# detector328p-au.net
KiCad netlist of a schematic drawn in EAGLE
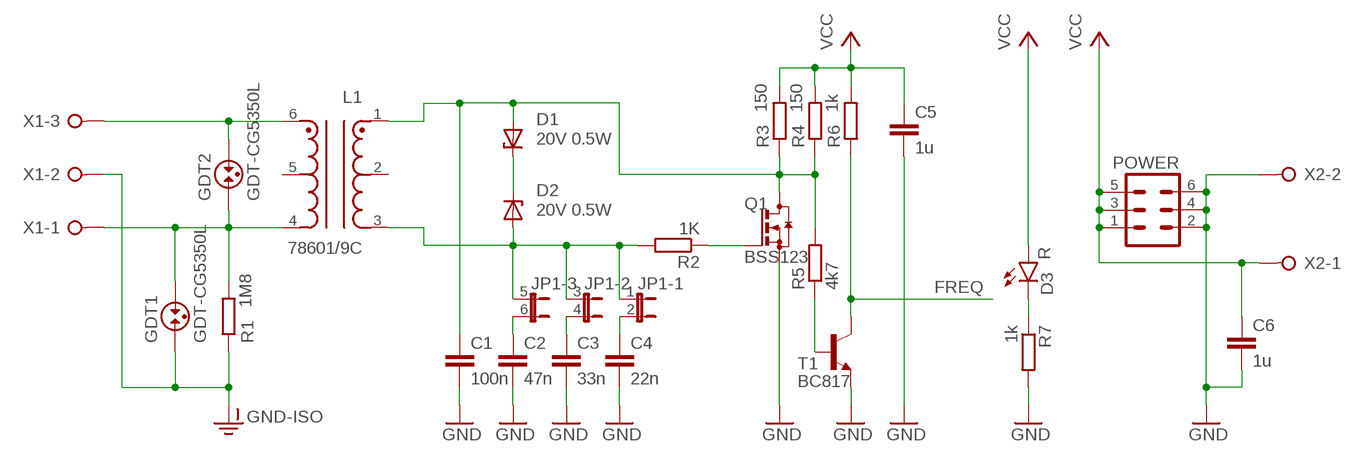
[diagram p0: schematic, sheet 1]
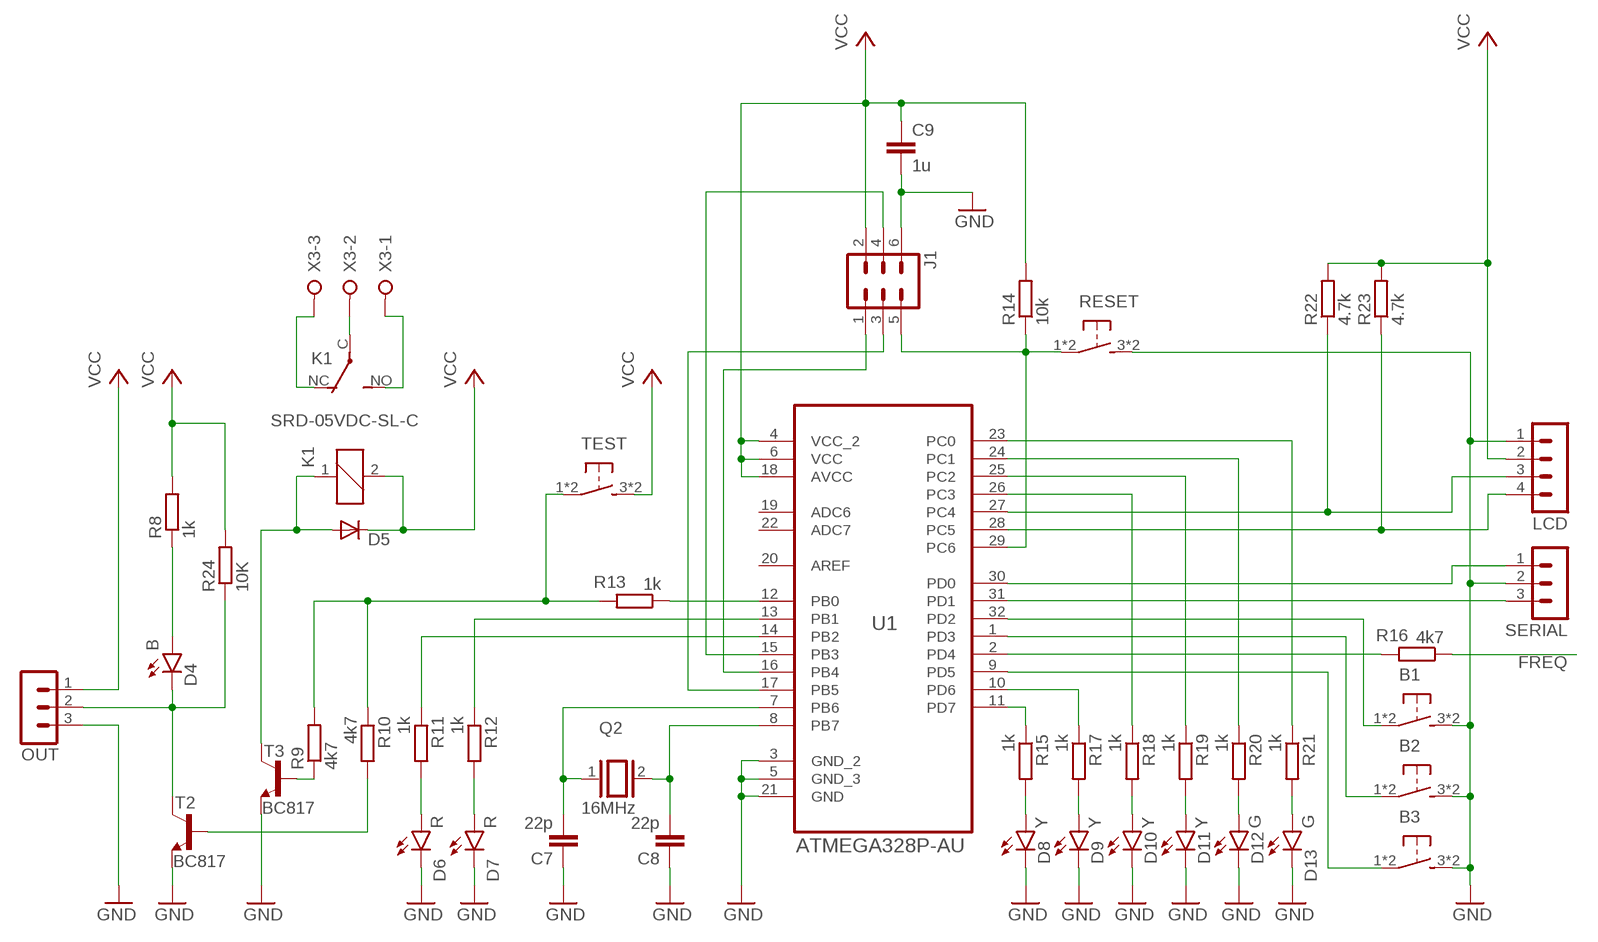
[diagram p1: schematic, sheet 2]

(export (version "E")
  (design (tool "Eeschema 10.0.6"))
  (components
    (comp (ref "B1")
      (value "10-XX")
      (footprint "eagle-import:B3F-10XX")
      (fields (field (name "MPN") "B3F-1000"))
      (libsource (lib "eagle-import") (part "10-XX"))
    )
    (comp (ref "B2")
      (value "10-XX")
      (footprint "eagle-import:B3F-10XX")
      (fields (field (name "MPN") "B3F-1000"))
      (libsource (lib "eagle-import") (part "10-XX"))
    )
    (comp (ref "B3")
      (value "10-XX")
      (footprint "eagle-import:B3F-10XX")
      (fields (field (name "MPN") "B3F-1000"))
      (libsource (lib "eagle-import") (part "10-XX"))
    )
    (comp (ref "C7")
      (value "22p")
      (footprint "eagle-import:C0603")
      (libsource (lib "eagle-import") (part "resistor_C-EUC0603"))
    )
    (comp (ref "C8")
      (value "22p")
      (footprint "eagle-import:C0603")
      (libsource (lib "eagle-import") (part "resistor_C-EUC0603"))
    )
    (comp (ref "C9")
      (value "1u")
      (footprint "eagle-import:C0603")
      (libsource (lib "eagle-import") (part "C-EUC0603"))
    )
    (comp (ref "D4")
      (value "B")
      (footprint "eagle-import:LED-0603")
      (libsource (lib "eagle-import") (part "LED0603"))
    )
    (comp (ref "D5")
      (value "DIODE-SOD80C")
      (footprint "eagle-import:SOD80C")
      (libsource (lib "eagle-import") (part "DIODE-SOD80C"))
    )
    (comp (ref "D6")
      (value "R")
      (footprint "eagle-import:LED-0603")
      (libsource (lib "eagle-import") (part "LED0603"))
    )
    (comp (ref "D7")
      (value "R")
      (footprint "eagle-import:LED-0603")
      (libsource (lib "eagle-import") (part "LED0603"))
    )
    (comp (ref "D8")
      (value "Y")
      (footprint "eagle-import:LED-0603")
      (libsource (lib "eagle-import") (part "LED0603"))
    )
    (comp (ref "D9")
      (value "Y")
      (footprint "eagle-import:LED-0603")
      (libsource (lib "eagle-import") (part "LED0603"))
    )
    (comp (ref "D10")
      (value "Y")
      (footprint "eagle-import:LED-0603")
      (libsource (lib "eagle-import") (part "LED0603"))
    )
    (comp (ref "D11")
      (value "Y")
      (footprint "eagle-import:LED-0603")
      (libsource (lib "eagle-import") (part "LED0603"))
    )
    (comp (ref "D12")
      (value "G")
      (footprint "eagle-import:LED-0603")
      (libsource (lib "eagle-import") (part "LED0603"))
    )
    (comp (ref "D13")
      (value "G")
      (footprint "eagle-import:LED-0603")
      (libsource (lib "eagle-import") (part "LED0603"))
    )
    (comp (ref "J1")
      (value "MA03-2")
      (footprint "eagle-import:MA03-2")
      (libsource (lib "eagle-import") (part "MA03-2"))
    )
    (comp (ref "K1")
      (value "SRD-05VDC-SL-C")
      (footprint "eagle-import:JS-M")
      (libsource (lib "eagle-import") (part "SRD--SL-C05VDC"))
    )
    (comp (ref "LCD")
      (value "MA04-1")
      (footprint "eagle-import:MA04-1")
      (libsource (lib "eagle-import") (part "MA04-1"))
    )
    (comp (ref "OUT")
      (value "MA03-1")
      (footprint "eagle-import:MA03-1")
      (libsource (lib "eagle-import") (part "MA03-1"))
    )
    (comp (ref "Q2")
      (value "16MHz")
      (footprint "eagle-import:QS")
      (libsource (lib "eagle-import") (part "XTAL/S"))
    )
    (comp (ref "R8")
      (value "1k")
      (footprint "eagle-import:R0603")
      (libsource (lib "eagle-import") (part "resistor_R-EU_R0603"))
    )
    (comp (ref "R9")
      (value "4k7")
      (footprint "eagle-import:R0603")
      (libsource (lib "eagle-import") (part "resistor_R-EU_R0603"))
    )
    (comp (ref "R10")
      (value "4k7")
      (footprint "eagle-import:R0603")
      (libsource (lib "eagle-import") (part "resistor_R-EU_R0603"))
    )
    (comp (ref "R11")
      (value "1k")
      (footprint "eagle-import:R0603")
      (libsource (lib "eagle-import") (part "resistor_R-EU_R0603"))
    )
    (comp (ref "R12")
      (value "1k")
      (footprint "eagle-import:R0603")
      (libsource (lib "eagle-import") (part "resistor_R-EU_R0603"))
    )
    (comp (ref "R13")
      (value "1k")
      (footprint "eagle-import:R0603")
      (libsource (lib "eagle-import") (part "resistor_R-EU_R0603"))
    )
    (comp (ref "R14")
      (value "10k")
      (footprint "eagle-import:R0603")
      (libsource (lib "eagle-import") (part "resistor_R-EU_R0603"))
    )
    (comp (ref "R15")
      (value "1k")
      (footprint "eagle-import:R0603")
      (libsource (lib "eagle-import") (part "resistor_R-EU_R0603"))
    )
    (comp (ref "R16")
      (value "4k7")
      (footprint "eagle-import:R0603")
      (libsource (lib "eagle-import") (part "resistor_R-EU_R0603"))
    )
    (comp (ref "R17")
      (value "1k")
      (footprint "eagle-import:R0603")
      (libsource (lib "eagle-import") (part "resistor_R-EU_R0603"))
    )
    (comp (ref "R18")
      (value "1k")
      (footprint "eagle-import:R0603")
      (libsource (lib "eagle-import") (part "resistor_R-EU_R0603"))
    )
    (comp (ref "R19")
      (value "1k")
      (footprint "eagle-import:R0603")
      (libsource (lib "eagle-import") (part "resistor_R-EU_R0603"))
    )
    (comp (ref "R20")
      (value "1k")
      (footprint "eagle-import:R0603")
      (libsource (lib "eagle-import") (part "resistor_R-EU_R0603"))
    )
    (comp (ref "R21")
      (value "1k")
      (footprint "eagle-import:R0603")
      (libsource (lib "eagle-import") (part "resistor_R-EU_R0603"))
    )
    (comp (ref "R22")
      (value "4.7k")
      (footprint "eagle-import:R0603")
      (libsource (lib "eagle-import") (part "R-EU_R0603"))
    )
    (comp (ref "R23")
      (value "4.7k")
      (footprint "eagle-import:R0603")
      (libsource (lib "eagle-import") (part "R-EU_R0603"))
    )
    (comp (ref "R24")
      (value "10K")
      (footprint "eagle-import:R0603")
      (libsource (lib "eagle-import") (part "resistor_R-EU_R0603"))
    )
    (comp (ref "RESET")
      (value "10-XX")
      (footprint "eagle-import:B3F-10XX")
      (fields (field (name "MPN") "B3F-1000"))
      (libsource (lib "eagle-import") (part "10-XX"))
    )
    (comp (ref "SERIAL")
      (value "MA03-1")
      (footprint "eagle-import:MA03-1")
      (libsource (lib "eagle-import") (part "MA03-1"))
    )
    (comp (ref "T2")
      (value "BC817")
      (footprint "eagle-import:SOT23-BEC")
      (libsource (lib "eagle-import") (part "BC817SMD-40"))
    )
    (comp (ref "T3")
      (value "BC817")
      (footprint "eagle-import:SOT23-BEC")
      (libsource (lib "eagle-import") (part "BC817SMD-40"))
    )
    (comp (ref "TEST")
      (value "10-XX")
      (footprint "eagle-import:B3F-10XX")
      (fields (field (name "MPN") "B3F-1000"))
      (libsource (lib "eagle-import") (part "10-XX"))
    )
    (comp (ref "U1")
      (value "ATMEGA328P-AU")
      (footprint "eagle-import:QFP80P900X900X120-32N")
      (libsource (lib "eagle-import") (part "ATMEGA328P-AU"))
    )
    (comp (ref "X3")
      (value "W237-3E")
      (footprint "eagle-import:W237-3E")
      (libsource (lib "eagle-import") (part "W237-3E"))
    )
    (comp (ref "C1")
      (value "100n")
      (footprint "eagle-import:C1206")
      (libsource (lib "eagle-import") (part "resistor_C-EUC1206"))
    )
    (comp (ref "C2")
      (value "47n")
      (footprint "eagle-import:C0805")
      (libsource (lib "eagle-import") (part "resistor_C-EUC0805"))
    )
    (comp (ref "C3")
      (value "33n")
      (footprint "eagle-import:C0805")
      (libsource (lib "eagle-import") (part "resistor_C-EUC0805"))
    )
    (comp (ref "C4")
      (value "22n")
      (footprint "eagle-import:C0805")
      (libsource (lib "eagle-import") (part "resistor_C-EUC0805"))
    )
    (comp (ref "C5")
      (value "1u")
      (footprint "eagle-import:C0603")
      (libsource (lib "eagle-import") (part "C-EUC0603"))
    )
    (comp (ref "C6")
      (value "1u")
      (footprint "eagle-import:C0603")
      (libsource (lib "eagle-import") (part "C-EUC0603"))
    )
    (comp (ref "D1")
      (value "20V 0.5W")
      (footprint "eagle-import:SOD80C")
      (libsource (lib "eagle-import") (part "ZENER-DIODESOD80C"))
    )
    (comp (ref "D2")
      (value "20V 0.5W")
      (footprint "eagle-import:SOD80C")
      (libsource (lib "eagle-import") (part "ZENER-DIODESOD80C"))
    )
    (comp (ref "D3")
      (value "R")
      (footprint "eagle-import:LED-0603")
      (libsource (lib "eagle-import") (part "LED0603"))
    )
    (comp (ref "GDT1")
      (value "GDT-CG5350L")
      (footprint "eagle-import:CG5350L")
      (libsource (lib "eagle-import") (part "GDT-CG5350L"))
    )
    (comp (ref "GDT2")
      (value "GDT-CG5350L")
      (footprint "eagle-import:CG5350L")
      (libsource (lib "eagle-import") (part "GDT-CG5350L"))
    )
    (comp (ref "JP1")
      (value "JP3QE")
      (footprint "eagle-import:JP3Q")
      (libsource (lib "eagle-import") (part "JP3QE"))
    )
    (comp (ref "L1")
      (value "78601/9C")
      (footprint "eagle-import:78601_9C")
      (libsource (lib "eagle-import") (part "78601/9C"))
    )
    (comp (ref "POWER")
      (value "MA03-2")
      (footprint "eagle-import:MA03-2")
      (libsource (lib "eagle-import") (part "MA03-2"))
    )
    (comp (ref "Q1")
      (value "BSS123")
      (footprint "eagle-import:SOT23")
      (libsource (lib "eagle-import") (part "BSS123"))
    )
    (comp (ref "R1")
      (value "1M8")
      (footprint "eagle-import:R0603")
      (libsource (lib "eagle-import") (part "resistor_R-EU_R0603"))
    )
    (comp (ref "R2")
      (value "1K")
      (footprint "eagle-import:R0603")
      (libsource (lib "eagle-import") (part "resistor_R-EU_R0603"))
    )
    (comp (ref "R3")
      (value "150")
      (footprint "eagle-import:R0603")
      (libsource (lib "eagle-import") (part "resistor_R-EU_R0603"))
    )
    (comp (ref "R4")
      (value "150")
      (footprint "eagle-import:R0603")
      (libsource (lib "eagle-import") (part "resistor_R-EU_R0603"))
    )
    (comp (ref "R5")
      (value "4k7")
      (footprint "eagle-import:R0603")
      (libsource (lib "eagle-import") (part "resistor_R-EU_R0603"))
    )
    (comp (ref "R6")
      (value "1k")
      (footprint "eagle-import:R0603")
      (libsource (lib "eagle-import") (part "resistor_R-EU_R0603"))
    )
    (comp (ref "R7")
      (value "1k")
      (footprint "eagle-import:R0603")
      (libsource (lib "eagle-import") (part "resistor_R-EU_R0603"))
    )
    (comp (ref "T1")
      (value "BC817")
      (footprint "eagle-import:SOT23-BEC")
      (libsource (lib "eagle-import") (part "BC817SMD-40"))
    )
    (comp (ref "X1")
      (value "W237-3E")
      (footprint "eagle-import:W237-3E")
      (libsource (lib "eagle-import") (part "W237-3E"))
    )
    (comp (ref "X2")
      (value "W237-02P")
      (footprint "eagle-import:W237-132")
      (libsource (lib "eagle-import") (part "W237-02P"))
    )
  )
  (nets
    (net (code "1") (name "FREQ") (class "Default")
      (node (ref "R16") (pin "1") (pinfunction "1_1") (pintype "passive"))
      (node (ref "R6") (pin "1") (pinfunction "1_1") (pintype "passive"))
      (node (ref "T1") (pin "C") (pinfunction "C_C") (pintype "passive"))
    )
    (net (code "2") (name "GND") (class "Default")
      (node (ref "B1") (pin "3") (pinfunction "S_3") (pintype "passive"))
      (node (ref "B1") (pin "4") (pinfunction "S_4") (pintype "passive"))
      (node (ref "B2") (pin "3") (pinfunction "S_3") (pintype "passive"))
      (node (ref "B2") (pin "4") (pinfunction "S_4") (pintype "passive"))
      (node (ref "B3") (pin "3") (pinfunction "S_3") (pintype "passive"))
      (node (ref "B3") (pin "4") (pinfunction "S_4") (pintype "passive"))
      (node (ref "C1") (pin "2") (pinfunction "2_2") (pintype "passive"))
      (node (ref "C2") (pin "2") (pinfunction "2_2") (pintype "passive"))
      (node (ref "C3") (pin "2") (pinfunction "2_2") (pintype "passive"))
      (node (ref "C4") (pin "2") (pinfunction "2_2") (pintype "passive"))
      (node (ref "C5") (pin "2") (pinfunction "2_2") (pintype "passive"))
      (node (ref "C6") (pin "2") (pinfunction "2_2") (pintype "passive"))
      (node (ref "C7") (pin "1") (pinfunction "1_1") (pintype "passive"))
      (node (ref "C8") (pin "1") (pinfunction "1_1") (pintype "passive"))
      (node (ref "C9") (pin "2") (pinfunction "2_2") (pintype "passive"))
      (node (ref "D10") (pin "C") (pinfunction "C_C") (pintype "passive"))
      (node (ref "D11") (pin "C") (pinfunction "C_C") (pintype "passive"))
      (node (ref "D12") (pin "C") (pinfunction "C_C") (pintype "passive"))
      (node (ref "D13") (pin "C") (pinfunction "C_C") (pintype "passive"))
      (node (ref "D6") (pin "C") (pinfunction "C_C") (pintype "passive"))
      (node (ref "D7") (pin "C") (pinfunction "C_C") (pintype "passive"))
      (node (ref "D8") (pin "C") (pinfunction "C_C") (pintype "passive"))
      (node (ref "D9") (pin "C") (pinfunction "C_C") (pintype "passive"))
      (node (ref "J1") (pin "6") (pinfunction "6_6") (pintype "passive"))
      (node (ref "LCD") (pin "1") (pinfunction "1_1") (pintype "passive"))
      (node (ref "OUT") (pin "3") (pinfunction "3_3") (pintype "passive"))
      (node (ref "POWER") (pin "2") (pinfunction "2_2") (pintype "passive"))
      (node (ref "POWER") (pin "4") (pinfunction "4_4") (pintype "passive"))
      (node (ref "POWER") (pin "6") (pinfunction "6_6") (pintype "passive"))
      (node (ref "Q1") (pin "2") (pinfunction "S_2") (pintype "passive"))
      (node (ref "R7") (pin "2") (pinfunction "2_2") (pintype "passive"))
      (node (ref "RESET") (pin "3") (pinfunction "S_3") (pintype "passive"))
      (node (ref "RESET") (pin "4") (pinfunction "S_4") (pintype "passive"))
      (node (ref "SERIAL") (pin "2") (pinfunction "2_2") (pintype "passive"))
      (node (ref "T1") (pin "E") (pinfunction "E_E") (pintype "passive"))
      (node (ref "T2") (pin "E") (pinfunction "E_E") (pintype "passive"))
      (node (ref "T3") (pin "E") (pinfunction "E_E") (pintype "passive"))
      (node (ref "U1") (pin "21") (pinfunction "GND_21") (pintype "passive"))
      (node (ref "U1") (pin "3") (pinfunction "GND_2_3") (pintype "passive"))
      (node (ref "U1") (pin "5") (pinfunction "GND_3_5") (pintype "passive"))
      (node (ref "X2") (pin "2") (pinfunction "KL_2") (pintype "passive"))
    )
    (net (code "3") (name "GND-ISO") (class "Default")
      (node (ref "GDT1") (pin "1") (pinfunction "1_1") (pintype "passive"))
      (node (ref "R1") (pin "1") (pinfunction "1_1") (pintype "passive"))
      (node (ref "X1") (pin "2") (pinfunction "KL_2") (pintype "passive"))
    )
    (net (code "4") (name "Net-(C4-Pad1)") (class "Default")
      (node (ref "C4") (pin "1") (pinfunction "1_1") (pintype "passive"))
      (node (ref "JP1") (pin "2") (pinfunction "2_2") (pintype "passive"))
    )
    (net (code "5") (name "Net-(D1-PadC)") (class "Default")
      (node (ref "D1") (pin "C") (pinfunction "C_C") (pintype "passive"))
      (node (ref "D2") (pin "C") (pinfunction "C_C") (pintype "passive"))
    )
    (net (code "6") (name "Net-(D3-PadC)") (class "Default")
      (node (ref "D3") (pin "C") (pinfunction "C_C") (pintype "passive"))
      (node (ref "R7") (pin "1") (pinfunction "1_1") (pintype "passive"))
    )
    (net (code "7") (name "Net-(D4-PadA)") (class "Default")
      (node (ref "D4") (pin "A") (pinfunction "A_A") (pintype "passive"))
      (node (ref "R8") (pin "1") (pinfunction "1_1") (pintype "passive"))
    )
    (net (code "8") (name "Net-(D4-PadC)") (class "Default")
      (node (ref "D4") (pin "C") (pinfunction "C_C") (pintype "passive"))
      (node (ref "OUT") (pin "2") (pinfunction "2_2") (pintype "passive"))
      (node (ref "R24") (pin "1") (pinfunction "1_1") (pintype "passive"))
      (node (ref "T2") (pin "C") (pinfunction "C_C") (pintype "passive"))
    )
    (net (code "9") (name "Net-(D5-PadA)") (class "Default")
      (node (ref "D5") (pin "A") (pinfunction "A_A") (pintype "passive"))
      (node (ref "K1") (pin "1") (pinfunction "1_1") (pintype "passive"))
      (node (ref "T3") (pin "C") (pinfunction "C_C") (pintype "passive"))
    )
    (net (code "10") (name "Net-(D6-PadA)") (class "Default")
      (node (ref "D6") (pin "A") (pinfunction "A_A") (pintype "passive"))
      (node (ref "R11") (pin "2") (pinfunction "2_2") (pintype "passive"))
    )
    (net (code "11") (name "Net-(D7-PadA)") (class "Default")
      (node (ref "D7") (pin "A") (pinfunction "A_A") (pintype "passive"))
      (node (ref "R12") (pin "2") (pinfunction "2_2") (pintype "passive"))
    )
    (net (code "12") (name "Net-(D8-PadA)") (class "Default")
      (node (ref "D8") (pin "A") (pinfunction "A_A") (pintype "passive"))
      (node (ref "R15") (pin "2") (pinfunction "2_2") (pintype "passive"))
    )
    (net (code "13") (name "Net-(D9-PadA)") (class "Default")
      (node (ref "D9") (pin "A") (pinfunction "A_A") (pintype "passive"))
      (node (ref "R17") (pin "2") (pinfunction "2_2") (pintype "passive"))
    )
    (net (code "14") (name "Net-(D10-PadA)") (class "Default")
      (node (ref "D10") (pin "A") (pinfunction "A_A") (pintype "passive"))
      (node (ref "R18") (pin "2") (pinfunction "2_2") (pintype "passive"))
    )
    (net (code "15") (name "Net-(D11-PadA)") (class "Default")
      (node (ref "D11") (pin "A") (pinfunction "A_A") (pintype "passive"))
      (node (ref "R19") (pin "2") (pinfunction "2_2") (pintype "passive"))
    )
    (net (code "16") (name "Net-(D12-PadA)") (class "Default")
      (node (ref "D12") (pin "A") (pinfunction "A_A") (pintype "passive"))
      (node (ref "R20") (pin "2") (pinfunction "2_2") (pintype "passive"))
    )
    (net (code "17") (name "Net-(D13-PadA)") (class "Default")
      (node (ref "D13") (pin "A") (pinfunction "A_A") (pintype "passive"))
      (node (ref "R21") (pin "2") (pinfunction "2_2") (pintype "passive"))
    )
    (net (code "18") (name "Net-(JP1B-1)") (class "Default")
      (node (ref "D2") (pin "A") (pinfunction "A_A") (pintype "passive"))
      (node (ref "JP1") (pin "1") (pinfunction "1_1") (pintype "passive"))
      (node (ref "JP1") (pin "3") (pinfunction "1_3") (pintype "passive"))
      (node (ref "JP1") (pin "5") (pinfunction "1_5") (pintype "passive"))
      (node (ref "L1") (pin "3") (pinfunction "3_3") (pintype "passive"))
      (node (ref "R2") (pin "2") (pinfunction "2_2") (pintype "passive"))
    )
    (net (code "19") (name "Net-(JP1B-2)") (class "Default")
      (node (ref "C3") (pin "1") (pinfunction "1_1") (pintype "passive"))
      (node (ref "JP1") (pin "4") (pinfunction "2_4") (pintype "passive"))
    )
    (net (code "20") (name "Net-(JP1C-2)") (class "Default")
      (node (ref "C2") (pin "1") (pinfunction "1_1") (pintype "passive"))
      (node (ref "JP1") (pin "6") (pinfunction "2_6") (pintype "passive"))
    )
    (net (code "21") (name "Net-(K1B-O)") (class "Default")
      (node (ref "K1") (pin "NC") (pinfunction "O_NC") (pintype "passive"))
      (node (ref "X3") (pin "3") (pinfunction "KL_3") (pintype "passive"))
    )
    (net (code "22") (name "Net-(K1B-P)") (class "Default")
      (node (ref "K1") (pin "C") (pinfunction "P_C") (pintype "passive"))
      (node (ref "X3") (pin "2") (pinfunction "KL_2") (pintype "passive"))
    )
    (net (code "23") (name "Net-(K1B-S)") (class "Default")
      (node (ref "K1") (pin "NO") (pinfunction "S_NO") (pintype "passive"))
      (node (ref "X3") (pin "1") (pinfunction "KL_1") (pintype "passive"))
    )
    (net (code "24") (name "Net-(Q1-D)") (class "Default")
      (node (ref "C1") (pin "1") (pinfunction "1_1") (pintype "passive"))
      (node (ref "D1") (pin "A") (pinfunction "A_A") (pintype "passive"))
      (node (ref "L1") (pin "1") (pinfunction "1_1") (pintype "passive"))
      (node (ref "Q1") (pin "3") (pinfunction "D_3") (pintype "passive"))
      (node (ref "R3") (pin "1") (pinfunction "1_1") (pintype "passive"))
      (node (ref "R4") (pin "1") (pinfunction "1_1") (pintype "passive"))
      (node (ref "R5") (pin "2") (pinfunction "2_2") (pintype "passive"))
    )
    (net (code "25") (name "Net-(Q1-G)") (class "Default")
      (node (ref "Q1") (pin "1") (pinfunction "G_1") (pintype "passive"))
      (node (ref "R2") (pin "1") (pinfunction "1_1") (pintype "passive"))
    )
    (net (code "26") (name "Net-(R5-Pad1)") (class "Default")
      (node (ref "R5") (pin "1") (pinfunction "1_1") (pintype "passive"))
      (node (ref "T1") (pin "B") (pinfunction "B_B") (pintype "passive"))
    )
    (net (code "27") (name "Net-(R9-Pad1)") (class "Default")
      (node (ref "R9") (pin "1") (pinfunction "1_1") (pintype "passive"))
      (node (ref "T3") (pin "B") (pinfunction "B_B") (pintype "passive"))
    )
    (net (code "28") (name "Net-(R10-Pad1)") (class "Default")
      (node (ref "R10") (pin "1") (pinfunction "1_1") (pintype "passive"))
      (node (ref "R13") (pin "2") (pinfunction "2_2") (pintype "passive"))
      (node (ref "R9") (pin "2") (pinfunction "2_2") (pintype "passive"))
      (node (ref "TEST") (pin "1") (pinfunction "P_1") (pintype "passive"))
      (node (ref "TEST") (pin "2") (pinfunction "P_2") (pintype "passive"))
    )
    (net (code "29") (name "Net-(R10-Pad2)") (class "Default")
      (node (ref "R10") (pin "2") (pinfunction "2_2") (pintype "passive"))
      (node (ref "T2") (pin "B") (pinfunction "B_B") (pintype "passive"))
    )
    (net (code "30") (name "Net-(U1-PB0)") (class "Default")
      (node (ref "R13") (pin "1") (pinfunction "1_1") (pintype "passive"))
      (node (ref "U1") (pin "12") (pinfunction "PB0_12") (pintype "bidirectional"))
    )
    (net (code "31") (name "Net-(U1-PB1)") (class "Default")
      (node (ref "R12") (pin "1") (pinfunction "1_1") (pintype "passive"))
      (node (ref "U1") (pin "13") (pinfunction "PB1_13") (pintype "bidirectional"))
    )
    (net (code "32") (name "Net-(U1-PB2)") (class "Default")
      (node (ref "R11") (pin "1") (pinfunction "1_1") (pintype "passive"))
      (node (ref "U1") (pin "14") (pinfunction "PB2_14") (pintype "bidirectional"))
    )
    (net (code "33") (name "Net-(U1-PB3)") (class "Default")
      (node (ref "J1") (pin "4") (pinfunction "4_4") (pintype "passive"))
      (node (ref "U1") (pin "15") (pinfunction "PB3_15") (pintype "bidirectional"))
    )
    (net (code "34") (name "Net-(U1-PB4)") (class "Default")
      (node (ref "J1") (pin "1") (pinfunction "1_1") (pintype "passive"))
      (node (ref "U1") (pin "16") (pinfunction "PB4_16") (pintype "bidirectional"))
    )
    (net (code "35") (name "Net-(U1-PB5)") (class "Default")
      (node (ref "J1") (pin "3") (pinfunction "3_3") (pintype "passive"))
      (node (ref "U1") (pin "17") (pinfunction "PB5_17") (pintype "bidirectional"))
    )
    (net (code "36") (name "Net-(U1-PB6)") (class "Default")
      (node (ref "C7") (pin "2") (pinfunction "2_2") (pintype "passive"))
      (node (ref "Q2") (pin "1") (pinfunction "1_1") (pintype "passive"))
      (node (ref "U1") (pin "7") (pinfunction "PB6_7") (pintype "bidirectional"))
    )
    (net (code "37") (name "Net-(U1-PB7)") (class "Default")
      (node (ref "C8") (pin "2") (pinfunction "2_2") (pintype "passive"))
      (node (ref "Q2") (pin "2") (pinfunction "2_2") (pintype "passive"))
      (node (ref "U1") (pin "8") (pinfunction "PB7_8") (pintype "bidirectional"))
    )
    (net (code "38") (name "Net-(U1-PC0)") (class "Default")
      (node (ref "R21") (pin "1") (pinfunction "1_1") (pintype "passive"))
      (node (ref "U1") (pin "23") (pinfunction "PC0_23") (pintype "bidirectional"))
    )
    (net (code "39") (name "Net-(U1-PC1)") (class "Default")
      (node (ref "R20") (pin "1") (pinfunction "1_1") (pintype "passive"))
      (node (ref "U1") (pin "24") (pinfunction "PC1_24") (pintype "bidirectional"))
    )
    (net (code "40") (name "Net-(U1-PC2)") (class "Default")
      (node (ref "R19") (pin "1") (pinfunction "1_1") (pintype "passive"))
      (node (ref "U1") (pin "25") (pinfunction "PC2_25") (pintype "bidirectional"))
    )
    (net (code "41") (name "Net-(U1-PC3)") (class "Default")
      (node (ref "R18") (pin "1") (pinfunction "1_1") (pintype "passive"))
      (node (ref "U1") (pin "26") (pinfunction "PC3_26") (pintype "bidirectional"))
    )
    (net (code "42") (name "Net-(U1-PC4)") (class "Default")
      (node (ref "LCD") (pin "3") (pinfunction "3_3") (pintype "passive"))
      (node (ref "R22") (pin "1") (pinfunction "1_1") (pintype "passive"))
      (node (ref "U1") (pin "27") (pinfunction "PC4_27") (pintype "bidirectional"))
    )
    (net (code "43") (name "Net-(U1-PC5)") (class "Default")
      (node (ref "LCD") (pin "4") (pinfunction "4_4") (pintype "passive"))
      (node (ref "R23") (pin "1") (pinfunction "1_1") (pintype "passive"))
      (node (ref "U1") (pin "28") (pinfunction "PC5_28") (pintype "bidirectional"))
    )
    (net (code "44") (name "Net-(U1-PC6)") (class "Default")
      (node (ref "J1") (pin "5") (pinfunction "5_5") (pintype "passive"))
      (node (ref "R14") (pin "1") (pinfunction "1_1") (pintype "passive"))
      (node (ref "RESET") (pin "1") (pinfunction "P_1") (pintype "passive"))
      (node (ref "RESET") (pin "2") (pinfunction "P_2") (pintype "passive"))
      (node (ref "U1") (pin "29") (pinfunction "PC6_29") (pintype "bidirectional"))
    )
    (net (code "45") (name "Net-(U1-PD0)") (class "Default")
      (node (ref "SERIAL") (pin "1") (pinfunction "1_1") (pintype "passive"))
      (node (ref "U1") (pin "30") (pinfunction "PD0_30") (pintype "bidirectional"))
    )
    (net (code "46") (name "Net-(U1-PD1)") (class "Default")
      (node (ref "SERIAL") (pin "3") (pinfunction "3_3") (pintype "passive"))
      (node (ref "U1") (pin "31") (pinfunction "PD1_31") (pintype "bidirectional"))
    )
    (net (code "47") (name "Net-(U1-PD2)") (class "Default")
      (node (ref "B1") (pin "1") (pinfunction "P_1") (pintype "passive"))
      (node (ref "B1") (pin "2") (pinfunction "P_2") (pintype "passive"))
      (node (ref "U1") (pin "32") (pinfunction "PD2_32") (pintype "bidirectional"))
    )
    (net (code "48") (name "Net-(U1-PD3)") (class "Default")
      (node (ref "B2") (pin "1") (pinfunction "P_1") (pintype "passive"))
      (node (ref "B2") (pin "2") (pinfunction "P_2") (pintype "passive"))
      (node (ref "U1") (pin "1") (pinfunction "PD3_1") (pintype "bidirectional"))
    )
    (net (code "49") (name "Net-(U1-PD4)") (class "Default")
      (node (ref "R16") (pin "2") (pinfunction "2_2") (pintype "passive"))
      (node (ref "U1") (pin "2") (pinfunction "PD4_2") (pintype "bidirectional"))
    )
    (net (code "50") (name "Net-(U1-PD5)") (class "Default")
      (node (ref "B3") (pin "1") (pinfunction "P_1") (pintype "passive"))
      (node (ref "B3") (pin "2") (pinfunction "P_2") (pintype "passive"))
      (node (ref "U1") (pin "9") (pinfunction "PD5_9") (pintype "bidirectional"))
    )
    (net (code "51") (name "Net-(U1-PD6)") (class "Default")
      (node (ref "R17") (pin "1") (pinfunction "1_1") (pintype "passive"))
      (node (ref "U1") (pin "10") (pinfunction "PD6_10") (pintype "bidirectional"))
    )
    (net (code "52") (name "Net-(U1-PD7)") (class "Default")
      (node (ref "R15") (pin "1") (pinfunction "1_1") (pintype "passive"))
      (node (ref "U1") (pin "11") (pinfunction "PD7_11") (pintype "bidirectional"))
    )
    (net (code "53") (name "Net-(X1A-KL)") (class "Default")
      (node (ref "GDT1") (pin "2") (pinfunction "2_2") (pintype "passive"))
      (node (ref "GDT2") (pin "1") (pinfunction "1_1") (pintype "passive"))
      (node (ref "L1") (pin "4") (pinfunction "4_4") (pintype "passive"))
      (node (ref "R1") (pin "2") (pinfunction "2_2") (pintype "passive"))
      (node (ref "X1") (pin "1") (pinfunction "KL_1") (pintype "passive"))
    )
    (net (code "54") (name "Net-(X1C-KL)") (class "Default")
      (node (ref "GDT2") (pin "2") (pinfunction "2_2") (pintype "passive"))
      (node (ref "L1") (pin "6") (pinfunction "6_6") (pintype "passive"))
      (node (ref "X1") (pin "3") (pinfunction "KL_3") (pintype "passive"))
    )
    (net (code "55") (name "VCC") (class "Default")
      (node (ref "C5") (pin "1") (pinfunction "1_1") (pintype "passive"))
      (node (ref "C6") (pin "1") (pinfunction "1_1") (pintype "passive"))
      (node (ref "C9") (pin "1") (pinfunction "1_1") (pintype "passive"))
      (node (ref "D3") (pin "A") (pinfunction "A_A") (pintype "passive"))
      (node (ref "D5") (pin "C") (pinfunction "C_C") (pintype "passive"))
      (node (ref "J1") (pin "2") (pinfunction "2_2") (pintype "passive"))
      (node (ref "K1") (pin "2") (pinfunction "2_2") (pintype "passive"))
      (node (ref "LCD") (pin "2") (pinfunction "2_2") (pintype "passive"))
      (node (ref "OUT") (pin "1") (pinfunction "1_1") (pintype "passive"))
      (node (ref "POWER") (pin "1") (pinfunction "1_1") (pintype "passive"))
      (node (ref "POWER") (pin "3") (pinfunction "3_3") (pintype "passive"))
      (node (ref "POWER") (pin "5") (pinfunction "5_5") (pintype "passive"))
      (node (ref "R14") (pin "2") (pinfunction "2_2") (pintype "passive"))
      (node (ref "R22") (pin "2") (pinfunction "2_2") (pintype "passive"))
      (node (ref "R23") (pin "2") (pinfunction "2_2") (pintype "passive"))
      (node (ref "R24") (pin "2") (pinfunction "2_2") (pintype "passive"))
      (node (ref "R3") (pin "2") (pinfunction "2_2") (pintype "passive"))
      (node (ref "R4") (pin "2") (pinfunction "2_2") (pintype "passive"))
      (node (ref "R6") (pin "2") (pinfunction "2_2") (pintype "passive"))
      (node (ref "R8") (pin "2") (pinfunction "2_2") (pintype "passive"))
      (node (ref "TEST") (pin "3") (pinfunction "S_3") (pintype "passive"))
      (node (ref "TEST") (pin "4") (pinfunction "S_4") (pintype "passive"))
      (node (ref "U1") (pin "18") (pinfunction "AVCC_18") (pintype "power_in"))
      (node (ref "U1") (pin "4") (pinfunction "VCC_2_4") (pintype "power_in"))
      (node (ref "U1") (pin "6") (pinfunction "VCC_6") (pintype "power_in"))
      (node (ref "X2") (pin "1") (pinfunction "KL_1") (pintype "passive"))
    )
    (net (code "56") (name "unconnected-(L1-Pad2)") (class "Default")
      (node (ref "L1") (pin "2") (pinfunction "2_2") (pintype "passive"))
    )
    (net (code "57") (name "unconnected-(L1-Pad5)") (class "Default")
      (node (ref "L1") (pin "5") (pinfunction "5_5") (pintype "passive"))
    )
    (net (code "58") (name "unconnected-(U1-ADC6-Pad19)") (class "Default")
      (node (ref "U1") (pin "19") (pinfunction "ADC6_19") (pintype "input"))
    )
    (net (code "59") (name "unconnected-(U1-ADC7-Pad22)") (class "Default")
      (node (ref "U1") (pin "22") (pinfunction "ADC7_22") (pintype "input"))
    )
    (net (code "60") (name "unconnected-(U1-AREF-Pad20)") (class "Default")
      (node (ref "U1") (pin "20") (pinfunction "AREF_20") (pintype "input"))
    )
  )
)
